# 1_P1.net
KiCad netlist of a schematic drawn in Altium Designer
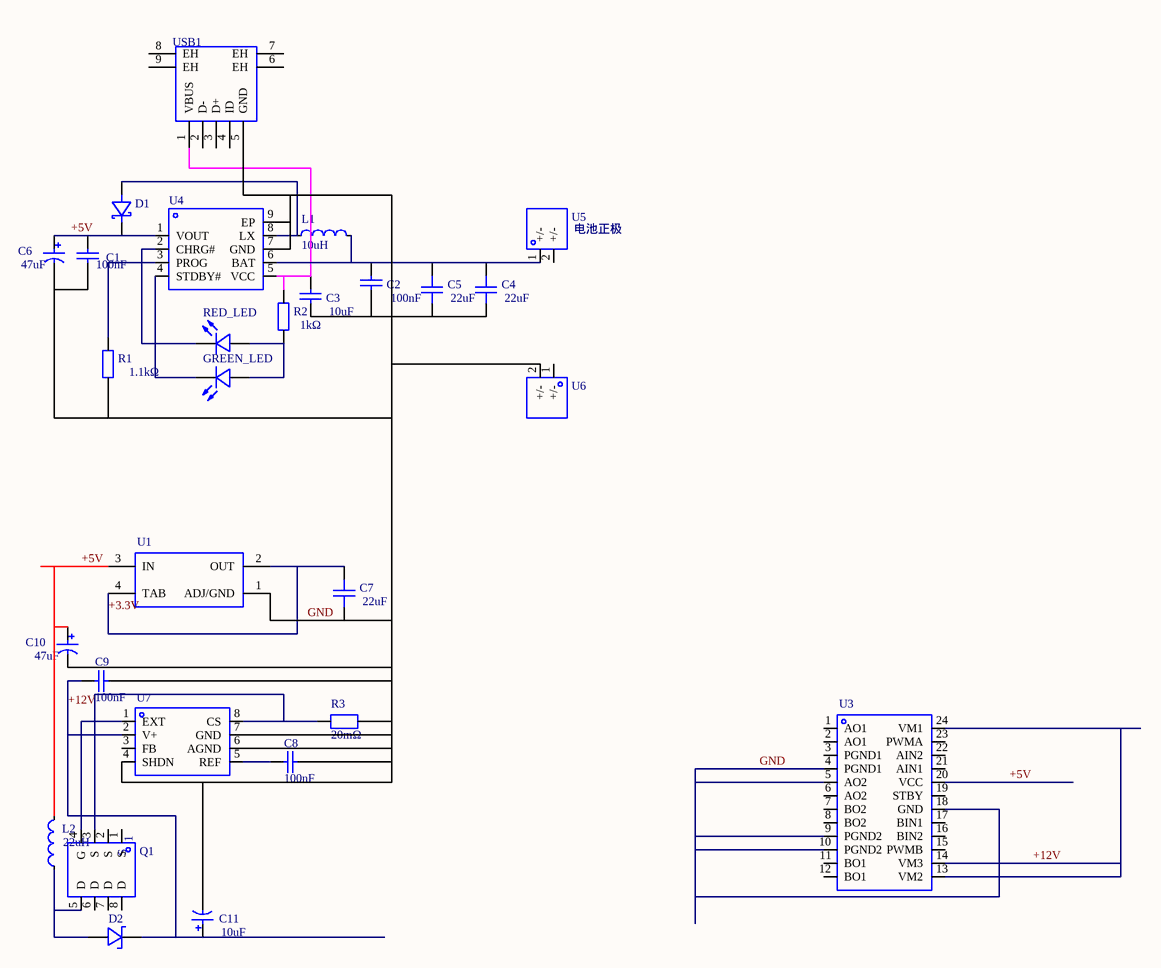
[diagram p0: 1_P1.schdoc]

(export (version "E")
  (design (tool "Eeschema 10.0.6"))
  (components
    (comp (ref "C1")
      (value "100nF")
      (fields
        (field (name "MANUFACTURER") "FH(风华)")
        (field (name "MANUFACTURER PART") "1206B104K500NT")
        (field (name "TOLERANCE") "±10%")
      )
      (libsource (lib "altium-import") (part "root_1_1206B104K500NT_"))
    )
    (comp (ref "C2")
      (value "100nF")
      (fields
        (field (name "MANUFACTURER") "FH(风华)")
        (field (name "MANUFACTURER PART") "1206B104K500NT")
        (field (name "TOLERANCE") "±10%")
      )
      (libsource (lib "altium-import") (part "root_1_1206B104K500NT_"))
    )
    (comp (ref "C3")
      (value "10uF")
      (fields
        (field (name "MANUFACTURER") "SAMSUNG(三星)")
        (field (name "MANUFACTURER PART") "CL31B106KOHNNNE")
        (field (name "TOLERANCE") "±10%")
      )
      (libsource (lib "altium-import") (part "root_1_CL31B106KOHNNNE_"))
    )
    (comp (ref "C4")
      (value "22uF")
      (fields
        (field (name "MANUFACTURER") "SAMSUNG(三星)")
        (field (name "MANUFACTURER PART") "CL31A226KOHNNNE")
        (field (name "TOLERANCE") "±10%")
      )
      (libsource (lib "altium-import") (part "root_1_CL31A226KOHNNNE_"))
    )
    (comp (ref "C5")
      (value "22uF")
      (fields
        (field (name "MANUFACTURER") "SAMSUNG(三星)")
        (field (name "MANUFACTURER PART") "CL31A226KOHNNNE")
        (field (name "TOLERANCE") "±10%")
      )
      (libsource (lib "altium-import") (part "root_1_CL31A226KOHNNNE_"))
    )
    (comp (ref "C6")
      (value "47uF")
      (fields
        (field (name "MANUFACTURER") "rubycon(红宝石)")
        (field (name "MANUFACTURER PART") "25YXF47MEFC5X11")
        (field (name "TOLERANCE") "±20%")
      )
      (libsource (lib "altium-import") (part "root_3_25YXF47MEFC5X11_"))
    )
    (comp (ref "C7")
      (value "22uF")
      (fields
        (field (name "MANUFACTURER") "SAMSUNG(三星)")
        (field (name "MANUFACTURER PART") "CL31A226KOHNNNE")
        (field (name "TOLERANCE") "±10%")
      )
      (libsource (lib "altium-import") (part "root_1_CL31A226KOHNNNE_"))
    )
    (comp (ref "C8")
      (value "100nF")
      (fields
        (field (name "MANUFACTURER") "FH(风华)")
        (field (name "MANUFACTURER PART") "1206B104K500NT")
        (field (name "TOLERANCE") "±10%")
      )
      (libsource (lib "altium-import") (part "root_2_1206B104K500NT_"))
    )
    (comp (ref "C9")
      (value "100nF")
      (fields
        (field (name "MANUFACTURER") "FH(风华)")
        (field (name "MANUFACTURER PART") "1206B104K500NT")
        (field (name "TOLERANCE") "±10%")
      )
      (libsource (lib "altium-import") (part "root_2_1206B104K500NT_"))
    )
    (comp (ref "C10")
      (value "47uF")
      (fields
        (field (name "MANUFACTURER") "rubycon(红宝石)")
        (field (name "MANUFACTURER PART") "25YXF47MEFC5X11")
        (field (name "TOLERANCE") "±20%")
      )
      (libsource (lib "altium-import") (part "root_3_25YXF47MEFC5X11_"))
    )
    (comp (ref "C11")
      (value "10uF")
      (fields
        (field (name "MANUFACTURER") "rubycon(红宝石)")
        (field (name "MANUFACTURER PART") "50YXF10MEFC5X11")
        (field (name "TOLERANCE") "±20%")
      )
      (libsource (lib "altium-import") (part "root_1_50YXF10MEFC5X11_"))
    )
    (comp (ref "D1")
      (value "~")
      (fields (field (name "MANUFACTURER") "Slkor(萨科微)") (field (name "MANUFACTURER PART") "SS32"))
      (libsource (lib "altium-import") (part "root_1_SS32_C5122584_"))
    )
    (comp (ref "D2")
      (value "~")
      (description "直流反向耐压(Vr):40V;平均整流电流(Io):1A;正向压降(Vf):600mV@1A;")
      (fields (field (name "MANUFACTURER") "Hottech(合科泰)") (field (name "MANUFACTURER PART") "1N5819WS"))
      (libsource (lib "altium-import") (part "root_2_1N5819WS_C191023_"))
    )
    (comp (ref "GREEN_LED")
      (value "~")
      (description "发光颜色:翠绿;")
      (fields (field (name "MANUFACTURER") "国星光电") (field (name "MANUFACTURER PART") "NCD0805G1"))
      (libsource (lib "altium-import") (part "root_2_NCD0805G1_"))
    )
    (comp (ref "L1")
      (value "10uH")
      (fields
        (field (name "MANUFACTURER") "cjiang(长江微电)")
        (field (name "MANUFACTURER PART") "FXL0420-100-M")
        (field (name "TOLERANCE") "±20%")
      )
      (libsource (lib "altium-import") (part "root_0_FXL0420-100-M_"))
    )
    (comp (ref "L2")
      (value "22uH")
      (fields
        (field (name "MANUFACTURER") "Sunlord(顺络)")
        (field (name "MANUFACTURER PART") "SWPA6045S220MT")
        (field (name "TOLERANCE") "±20%")
      )
      (libsource (lib "altium-import") (part "root_1_SWPA6045S220MT_"))
    )
    (comp (ref "Q1")
      (value "~")
      (fields
        (field (name "MANUFACTURER") "VBsemi(台湾微碧)")
        (field (name "MANUFACTURER PART") "SI9410BDY-T1")
        (field (name "NAME") "S")
        (field (name "NUMBER") "1")
      )
      (libsource (lib "altium-import") (part "root_3_SI9410BDY-T1_"))
    )
    (comp (ref "R1")
      (value "1.1kΩ")
      (fields
        (field (name "MANUFACTURER") "RESI(开步睿思）")
        (field (name "MANUFACTURER PART") "AECR1206F1K10K9")
        (field (name "TOLERANCE") "±1%")
      )
      (libsource (lib "altium-import") (part "root_1_AECR1206F1K10K9_"))
    )
    (comp (ref "R2")
      (value "1kΩ")
      (fields
        (field (name "MANUFACTURER") "UNI-ROYAL(厚声)")
        (field (name "MANUFACTURER PART") "1206W4J0102T5E")
        (field (name "TOLERANCE") "±5%")
      )
      (libsource (lib "altium-import") (part "root_1_1206W4J0102T5E_"))
    )
    (comp (ref "R3")
      (value "20mΩ")
      (fields
        (field (name "MANUFACTURER") "UNI-ROYAL(厚声)")
        (field (name "MANUFACTURER PART") "1206W3F200MT5E")
        (field (name "TOLERANCE") "±1%")
      )
      (libsource (lib "altium-import") (part "root_0_1206W3F200MT5E_"))
    )
    (comp (ref "RED_LED")
      (value "~")
      (description "发光颜色:红灯;")
      (fields (field (name "MANUFACTURER") "国星光电") (field (name "MANUFACTURER PART") "NCD0805R1"))
      (libsource (lib "altium-import") (part "root_0_NCD0805R1_"))
    )
    (comp (ref "U1")
      (value "~")
      (description "输出类型:固定;输出极性:正;输出通道数:1;最大输入电压:12V;输出电压:3.3V;压差:1.5V@(3A);输出电流:3A;电源纹波抑制比(PRSS):-;")
      (fields (field (name "MANUFACTURER") "HTC") (field (name "MANUFACTURER PART") "LM1085R-3.3"))
      (libsource (lib "altium-import") (part "root_0_LM1085R-3.3_"))
    )
    (comp (ref "U3")
      (value "~")
      (description "双直流电机驱动器集成电路")
      (fields
        (field (name "MANUFACTURER") "TOSHIBA(东芝)")
        (field (name "MANUFACTURER PART") "TB6612FNG(O,C,8,EL")
      )
      (libsource (lib "altium-import") (part "root_0_TB6612FNG(O,C,8,EL_"))
    )
    (comp (ref "U4")
      (value "~")
      (fields (field (name "MANUFACTURER") "TOPPOWER(南京拓微)") (field (name "MANUFACTURER PART") "TP5400"))
      (libsource (lib "altium-import") (part "root_0_TP5400_"))
    )
    (comp (ref "U5")
      (value "电池正极")
      (description "18650电池夹")
      (fields
        (field (name "NAME") "电池正极")
        (field (name "MANUFACTURER") "MYOUNG(美阳)")
        (field (name "MANUFACTURER PART") "MY-18650-02")
      )
      (libsource (lib "altium-import") (part "root_1_MY-18650-02_"))
    )
    (comp (ref "U6")
      (value "电池负极")
      (description "18650电池夹")
      (fields (field (name "MANUFACTURER") "MYOUNG(美阳)") (field (name "MANUFACTURER PART") "MY-18650-02"))
      (libsource (lib "altium-import") (part "root_3_MY-18650-02_"))
    )
    (comp (ref "U7")
      (value "~")
      (description "功能类型:升降压型;同步整流:否;输出通道数:1;拓扑结构:升降压式；升压式;输入电压:3V~16.5V;开关频率:300kHz;占空比(最大值):92%;工作温度:-40~+85@(TA);")
      (fields (field (name "MANUFACTURER") "MAXIM(美信)") (field (name "MANUFACTURER PART") "MAX1771ESA+T"))
      (libsource (lib "altium-import") (part "root_0_MAX1771ESA+T_"))
    )
    (comp (ref "USB1")
      (value "~")
      (description "连接器类型:Micro-B;标准:USB 2.0;公母:母座;触点数量:5;端口数量:1;安装方式:卧贴;额定电流 - 电源:-;工作温度范围:-30~+80;")
      (fields
        (field (name "MANUFACTURER") "kinghelm(金航标)")
        (field (name "MANUFACTURER PART") "KH-MICRO-SMT.ZJ-5P")
      )
      (libsource (lib "altium-import") (part "root_1_KH-MICRO-SMT.ZJ-5P_"))
    )
  )
  (nets
    (net (code "1") (name "/+3.3V") (class "Default")
      (node (ref "C7") (pin "2") (pinfunction "2_2") (pintype "passive"))
      (node (ref "U1") (pin "2") (pinfunction "OUT_2") (pintype "passive"))
      (node (ref "U1") (pin "4") (pinfunction "TAB_4") (pintype "passive"))
    )
    (net (code "2") (name "/+5V") (class "Default")
      (node (ref "C1") (pin "2") (pinfunction "2_2") (pintype "passive"))
      (node (ref "C10") (pin "1") (pinfunction "1_1") (pintype "passive"))
      (node (ref "C6") (pin "1") (pinfunction "1_1") (pintype "passive"))
      (node (ref "D1") (pin "1") (pinfunction "1_1") (pintype "passive"))
      (node (ref "L2") (pin "2") (pinfunction "2_2") (pintype "passive"))
      (node (ref "U1") (pin "3") (pinfunction "IN_3") (pintype "passive"))
      (node (ref "U3") (pin "20") (pinfunction "VCC_20") (pintype "passive"))
      (node (ref "U4") (pin "1") (pinfunction "VOUT_1") (pintype "passive"))
    )
    (net (code "3") (name "/+12V") (class "Default")
      (node (ref "C11") (pin "1") (pinfunction "1_1") (pintype "passive"))
      (node (ref "C9") (pin "2") (pinfunction "2_2") (pintype "passive"))
      (node (ref "D2") (pin "1") (pinfunction "C_1") (pintype "passive"))
      (node (ref "U3") (pin "13") (pinfunction "VM2_13") (pintype "passive"))
      (node (ref "U3") (pin "14") (pinfunction "VM3_14") (pintype "passive"))
      (node (ref "U3") (pin "24") (pinfunction "VM1_24") (pintype "passive"))
      (node (ref "U7") (pin "2") (pinfunction "V+_2") (pintype "passive"))
    )
    (net (code "4") (name "/GND") (class "Default")
      (node (ref "C1") (pin "1") (pinfunction "1_1") (pintype "passive"))
      (node (ref "C10") (pin "2") (pinfunction "2_2") (pintype "passive"))
      (node (ref "C11") (pin "2") (pinfunction "2_2") (pintype "passive"))
      (node (ref "C2") (pin "1") (pinfunction "1_1") (pintype "passive"))
      (node (ref "C3") (pin "1") (pinfunction "1_1") (pintype "passive"))
      (node (ref "C4") (pin "1") (pinfunction "1_1") (pintype "passive"))
      (node (ref "C5") (pin "1") (pinfunction "1_1") (pintype "passive"))
      (node (ref "C6") (pin "2") (pinfunction "2_2") (pintype "passive"))
      (node (ref "C7") (pin "1") (pinfunction "1_1") (pintype "passive"))
      (node (ref "C8") (pin "1") (pinfunction "1_1") (pintype "passive"))
      (node (ref "C9") (pin "1") (pinfunction "1_1") (pintype "passive"))
      (node (ref "R1") (pin "1") (pinfunction "1_1") (pintype "passive"))
      (node (ref "R3") (pin "2") (pinfunction "2_2") (pintype "passive"))
      (node (ref "U1") (pin "1") (pinfunction "ADJ/GND_1") (pintype "passive"))
      (node (ref "U3") (pin "10") (pinfunction "PGND2_10") (pintype "passive"))
      (node (ref "U3") (pin "18") (pinfunction "GND_18") (pintype "passive"))
      (node (ref "U3") (pin "4") (pinfunction "PGND1_4") (pintype "passive"))
      (node (ref "U3") (pin "5") (pinfunction "AO2_5") (pintype "passive"))
      (node (ref "U3") (pin "9") (pinfunction "PGND2_9") (pintype "passive"))
      (node (ref "U4") (pin "7") (pinfunction "GND_7") (pintype "passive"))
      (node (ref "U4") (pin "9") (pinfunction "EP_9") (pintype "passive"))
      (node (ref "U6") (pin "2") (pinfunction "+/-_2") (pintype "passive"))
      (node (ref "U7") (pin "4") (pinfunction "SHDN_4") (pintype "passive"))
      (node (ref "U7") (pin "6") (pinfunction "AGND_6") (pintype "passive"))
      (node (ref "U7") (pin "7") (pinfunction "GND_7") (pintype "passive"))
      (node (ref "USB1") (pin "5") (pinfunction "GND_5") (pintype "passive"))
    )
    (net (code "5") (name "Net-(D2-A)") (class "Default")
      (node (ref "D2") (pin "2") (pinfunction "A_2") (pintype "passive"))
      (node (ref "L2") (pin "1") (pinfunction "1_1") (pintype "passive"))
      (node (ref "Q1") (pin "5") (pinfunction "D_5") (pintype "passive"))
    )
    (net (code "6") (name "Net-(GREEN_LED-A)") (class "Default")
      (node (ref "GREEN_LED") (pin "1") (pinfunction "A_1") (pintype "passive"))
      (node (ref "R2") (pin "1") (pinfunction "1_1") (pintype "passive"))
      (node (ref "RED_LED") (pin "2") (pinfunction "+_2") (pintype "passive"))
    )
    (net (code "7") (name "Net-(GREEN_LED-K)") (class "Default")
      (node (ref "GREEN_LED") (pin "2") (pinfunction "K_2") (pintype "passive"))
      (node (ref "U4") (pin "4") (pinfunction "STDBY#_4") (pintype "passive"))
    )
    (net (code "8") (name "Net-(Q1-G)") (class "Default")
      (node (ref "Q1") (pin "4") (pinfunction "G_4") (pintype "passive"))
      (node (ref "U7") (pin "1") (pinfunction "EXT_1") (pintype "passive"))
    )
    (net (code "9") (name "Net-(RED_LED--)") (class "Default")
      (node (ref "RED_LED") (pin "1") (pinfunction "-_1") (pintype "passive"))
      (node (ref "U4") (pin "2") (pinfunction "CHRG#_2") (pintype "passive"))
    )
    (net (code "10") (name "Net-(U4-BAT)") (class "Default")
      (node (ref "C2") (pin "2") (pinfunction "2_2") (pintype "passive"))
      (node (ref "C4") (pin "2") (pinfunction "2_2") (pintype "passive"))
      (node (ref "C5") (pin "2") (pinfunction "2_2") (pintype "passive"))
      (node (ref "L1") (pin "2") (pinfunction "2_2") (pintype "passive"))
      (node (ref "U4") (pin "6") (pinfunction "BAT_6") (pintype "passive"))
      (node (ref "U5") (pin "1") (pinfunction "+/-_1") (pintype "passive"))
    )
    (net (code "11") (name "Net-(U4-LX)") (class "Default")
      (node (ref "D1") (pin "2") (pinfunction "2_2") (pintype "passive"))
      (node (ref "L1") (pin "1") (pinfunction "1_1") (pintype "passive"))
      (node (ref "U4") (pin "8") (pinfunction "LX_8") (pintype "passive"))
    )
    (net (code "12") (name "Net-(U4-PROG)") (class "Default")
      (node (ref "R1") (pin "2") (pinfunction "2_2") (pintype "passive"))
      (node (ref "U4") (pin "3") (pinfunction "PROG_3") (pintype "passive"))
    )
    (net (code "13") (name "Net-(U4-VCC)") (class "Default")
      (node (ref "C3") (pin "2") (pinfunction "2_2") (pintype "passive"))
      (node (ref "R2") (pin "2") (pinfunction "2_2") (pintype "passive"))
      (node (ref "U4") (pin "5") (pinfunction "VCC_5") (pintype "passive"))
      (node (ref "USB1") (pin "1") (pinfunction "VBUS_1") (pintype "passive"))
    )
    (net (code "14") (name "Net-(U7-CS)") (class "Default")
      (node (ref "Q1") (pin "3") (pinfunction "S_3") (pintype "passive"))
      (node (ref "R3") (pin "1") (pinfunction "1_1") (pintype "passive"))
      (node (ref "U7") (pin "8") (pinfunction "CS_8") (pintype "passive"))
    )
    (net (code "15") (name "Net-(U7-REF)") (class "Default")
      (node (ref "C8") (pin "2") (pinfunction "2_2") (pintype "passive"))
      (node (ref "U7") (pin "5") (pinfunction "REF_5") (pintype "passive"))
    )
    (net (code "16") (name "unconnected-(Q1-D-Pad6)") (class "Default")
      (node (ref "Q1") (pin "6") (pinfunction "D_6") (pintype "passive"))
    )
    (net (code "17") (name "unconnected-(Q1-D-Pad7)") (class "Default")
      (node (ref "Q1") (pin "7") (pinfunction "D_7") (pintype "passive"))
    )
    (net (code "18") (name "unconnected-(Q1-D-Pad8)") (class "Default")
      (node (ref "Q1") (pin "8") (pinfunction "D_8") (pintype "passive"))
    )
    (net (code "19") (name "unconnected-(Q1-S-Pad1)") (class "Default")
      (node (ref "Q1") (pin "1") (pinfunction "S_1") (pintype "passive"))
    )
    (net (code "20") (name "unconnected-(Q1-S-Pad2)") (class "Default")
      (node (ref "Q1") (pin "2") (pinfunction "S_2") (pintype "passive"))
    )
    (net (code "21") (name "unconnected-(U3-AIN1-Pad21)") (class "Default")
      (node (ref "U3") (pin "21") (pinfunction "AIN1_21") (pintype "passive"))
    )
    (net (code "22") (name "unconnected-(U3-AIN2-Pad22)") (class "Default")
      (node (ref "U3") (pin "22") (pinfunction "AIN2_22") (pintype "passive"))
    )
    (net (code "23") (name "unconnected-(U3-AO1-Pad1)") (class "Default")
      (node (ref "U3") (pin "1") (pinfunction "AO1_1") (pintype "passive"))
    )
    (net (code "24") (name "unconnected-(U3-AO1-Pad2)") (class "Default")
      (node (ref "U3") (pin "2") (pinfunction "AO1_2") (pintype "passive"))
    )
    (net (code "25") (name "unconnected-(U3-AO2-Pad6)") (class "Default")
      (node (ref "U3") (pin "6") (pinfunction "AO2_6") (pintype "passive"))
    )
    (net (code "26") (name "unconnected-(U3-BIN1-Pad17)") (class "Default")
      (node (ref "U3") (pin "17") (pinfunction "BIN1_17") (pintype "passive"))
    )
    (net (code "27") (name "unconnected-(U3-BIN2-Pad16)") (class "Default")
      (node (ref "U3") (pin "16") (pinfunction "BIN2_16") (pintype "passive"))
    )
    (net (code "28") (name "unconnected-(U3-BO1-Pad11)") (class "Default")
      (node (ref "U3") (pin "11") (pinfunction "BO1_11") (pintype "passive"))
    )
    (net (code "29") (name "unconnected-(U3-BO1-Pad12)") (class "Default")
      (node (ref "U3") (pin "12") (pinfunction "BO1_12") (pintype "passive"))
    )
    (net (code "30") (name "unconnected-(U3-BO2-Pad7)") (class "Default")
      (node (ref "U3") (pin "7") (pinfunction "BO2_7") (pintype "passive"))
    )
    (net (code "31") (name "unconnected-(U3-BO2-Pad8)") (class "Default")
      (node (ref "U3") (pin "8") (pinfunction "BO2_8") (pintype "passive"))
    )
    (net (code "32") (name "unconnected-(U3-PGND1-Pad3)") (class "Default")
      (node (ref "U3") (pin "3") (pinfunction "PGND1_3") (pintype "passive"))
    )
    (net (code "33") (name "unconnected-(U3-PWMA-Pad23)") (class "Default")
      (node (ref "U3") (pin "23") (pinfunction "PWMA_23") (pintype "passive"))
    )
    (net (code "34") (name "unconnected-(U3-PWMB-Pad15)") (class "Default")
      (node (ref "U3") (pin "15") (pinfunction "PWMB_15") (pintype "passive"))
    )
    (net (code "35") (name "unconnected-(U3-STBY-Pad19)") (class "Default")
      (node (ref "U3") (pin "19") (pinfunction "STBY_19") (pintype "passive"))
    )
    (net (code "36") (name "unconnected-(U5-+{slash}--Pad2)") (class "Default")
      (node (ref "U5") (pin "2") (pinfunction "+/-_2") (pintype "passive"))
    )
    (net (code "37") (name "unconnected-(U6-+{slash}--Pad1)") (class "Default")
      (node (ref "U6") (pin "1") (pinfunction "+/-_1") (pintype "passive"))
    )
    (net (code "38") (name "unconnected-(U7-FB-Pad3)") (class "Default")
      (node (ref "U7") (pin "3") (pinfunction "FB_3") (pintype "passive"))
    )
    (net (code "39") (name "unconnected-(USB1-D+-Pad3)") (class "Default")
      (node (ref "USB1") (pin "3") (pinfunction "D+_3") (pintype "passive"))
    )
    (net (code "40") (name "unconnected-(USB1-D--Pad2)") (class "Default")
      (node (ref "USB1") (pin "2") (pinfunction "D-_2") (pintype "passive"))
    )
    (net (code "41") (name "unconnected-(USB1-EH-Pad6)") (class "Default")
      (node (ref "USB1") (pin "6") (pinfunction "EH_6") (pintype "passive"))
    )
    (net (code "42") (name "unconnected-(USB1-EH-Pad7)") (class "Default")
      (node (ref "USB1") (pin "7") (pinfunction "EH_7") (pintype "passive"))
    )
    (net (code "43") (name "unconnected-(USB1-EH-Pad8)") (class "Default")
      (node (ref "USB1") (pin "8") (pinfunction "EH_8") (pintype "passive"))
    )
    (net (code "44") (name "unconnected-(USB1-EH-Pad9)") (class "Default")
      (node (ref "USB1") (pin "9") (pinfunction "EH_9") (pintype "passive"))
    )
    (net (code "45") (name "unconnected-(USB1-ID-Pad4)") (class "Default")
      (node (ref "USB1") (pin "4") (pinfunction "ID_4") (pintype "passive"))
    )
  )
)
